# Main_Board.net
KiCad netlist of a schematic drawn in EAGLE
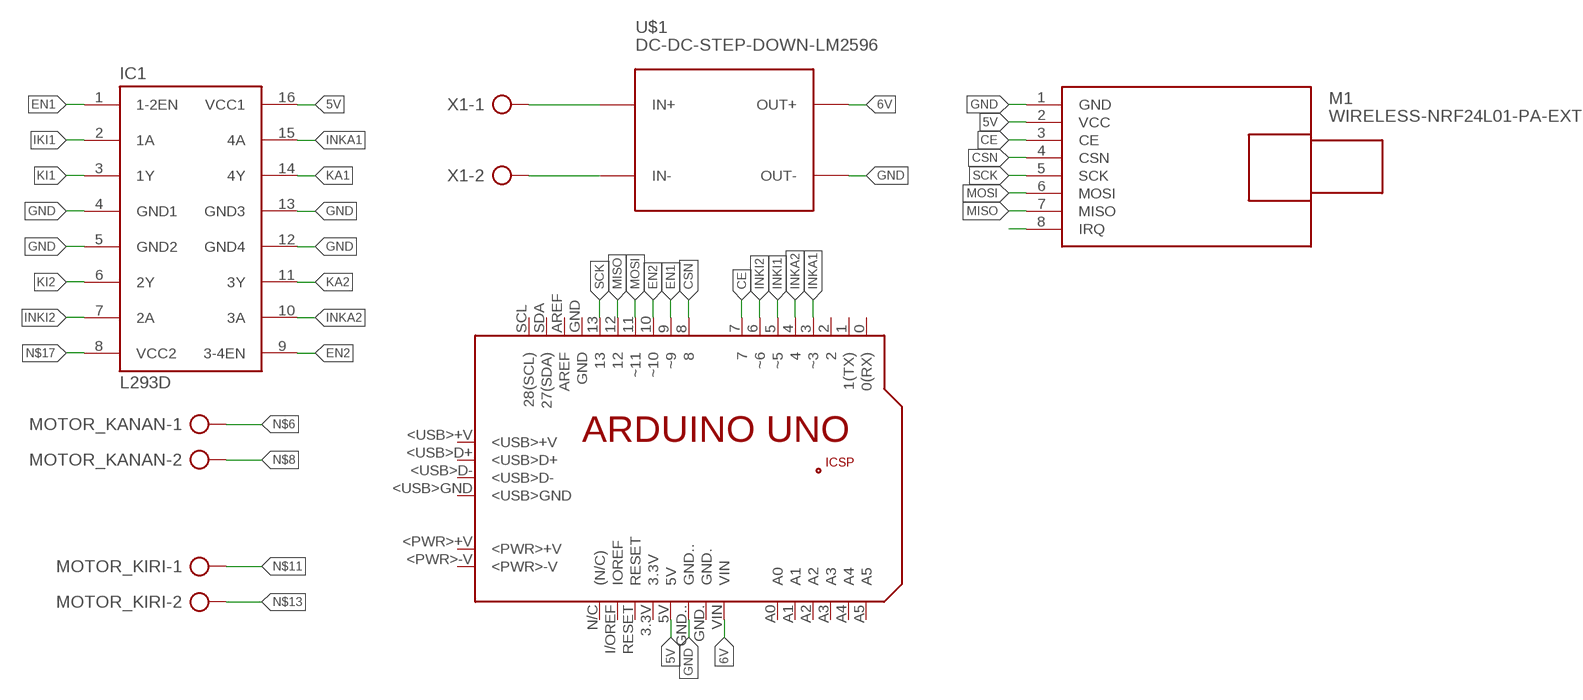
[diagram p0: schematic, sheet 1]

(export (version "E")
  (design (tool "Eeschema 10.0.6"))
  (components
    (comp (ref "IC1")
      (value "L293D")
      (footprint "eagle-import:DIL16")
      (libsource (lib "eagle-import") (part "L293D"))
    )
    (comp (ref "M1")
      (value "WIRELESS-NRF24L01-PA-EXT")
      (footprint "eagle-import:WIRELESS-NRF24L01-PA-EXT")
      (libsource (lib "eagle-import") (part "WIRELESS-NRF24L01-PA-EXT"))
    )
    (comp (ref "MOTOR_KANAN")
      (value "AK500/2-H")
      (footprint "eagle-import:AK500_2-H")
      (libsource (lib "eagle-import") (part "AK500/2-H"))
    )
    (comp (ref "MOTOR_KIRI")
      (value "AK500/2-H")
      (footprint "eagle-import:AK500_2-H")
      (libsource (lib "eagle-import") (part "AK500/2-H"))
    )
    (comp (ref "PCB1")
      (value "ARDUINO_UNO")
      (footprint "eagle-import:ARDUINO_UNO")
      (libsource (lib "eagle-import") (part "ARDUINO_UNO"))
    )
    (comp (ref "U$1")
      (value "DC-DC-STEP-DOWN-LM2596")
      (footprint "eagle-import:DC-DC-STEP-DOWN-LM2596")
      (libsource (lib "eagle-import") (part "DC-DC-STEP-DOWN-LM2596"))
    )
    (comp (ref "X1")
      (value "AK300/2")
      (footprint "eagle-import:AK300_2")
      (libsource (lib "eagle-import") (part "AK300/2"))
    )
  )
  (nets
    (net (code "1") (name "5V") (class "Default")
      (node (ref "IC1") (pin "16") (pinfunction "VCC1_16") (pintype "power_in"))
      (node (ref "M1") (pin "2") (pinfunction "VCC_2") (pintype "power_in"))
      (node (ref "PCB1") (pin "5V") (pinfunction "5V_5V") (pintype "bidirectional"))
    )
    (net (code "2") (name "6V") (class "Default")
      (node (ref "PCB1") (pin "VIN") (pinfunction "VIN_VIN") (pintype "bidirectional"))
      (node (ref "U$1") (pin "OUT+") (pinfunction "OUT+_OUT+") (pintype "bidirectional"))
    )
    (net (code "3") (name "CE") (class "Default")
      (node (ref "M1") (pin "3") (pinfunction "CE_3") (pintype "bidirectional"))
      (node (ref "PCB1") (pin "7") (pinfunction "7_7") (pintype "bidirectional"))
    )
    (net (code "4") (name "CSN") (class "Default")
      (node (ref "M1") (pin "4") (pinfunction "CSN_4") (pintype "bidirectional"))
      (node (ref "PCB1") (pin "8") (pinfunction "8_8") (pintype "bidirectional"))
    )
    (net (code "5") (name "EN1") (class "Default")
      (node (ref "IC1") (pin "1") (pinfunction "1-2EN_1") (pintype "input"))
      (node (ref "PCB1") (pin "9") (pinfunction "~{9}_9") (pintype "bidirectional"))
    )
    (net (code "6") (name "EN2") (class "Default")
      (node (ref "IC1") (pin "9") (pinfunction "3-4EN_9") (pintype "input"))
      (node (ref "PCB1") (pin "10") (pinfunction "~{10}_10") (pintype "bidirectional"))
    )
    (net (code "7") (name "GND") (class "Default")
      (node (ref "IC1") (pin "12") (pinfunction "GND4_12") (pintype "power_in"))
      (node (ref "IC1") (pin "13") (pinfunction "GND3_13") (pintype "power_in"))
      (node (ref "IC1") (pin "4") (pinfunction "GND1_4") (pintype "power_in"))
      (node (ref "IC1") (pin "5") (pinfunction "GND2_5") (pintype "power_in"))
      (node (ref "M1") (pin "1") (pinfunction "GND_1") (pintype "power_in"))
      (node (ref "PCB1") (pin "GND..") (pinfunction "GND.._GND..") (pintype "bidirectional"))
      (node (ref "U$1") (pin "OUT-") (pinfunction "OUT-_OUT-") (pintype "bidirectional"))
    )
    (net (code "8") (name "IKI1") (class "Default")
      (node (ref "IC1") (pin "2") (pinfunction "1A_2") (pintype "input"))
    )
    (net (code "9") (name "INKA1") (class "Default")
      (node (ref "IC1") (pin "15") (pinfunction "4A_15") (pintype "input"))
      (node (ref "PCB1") (pin "3") (pinfunction "~{3}_3") (pintype "bidirectional"))
    )
    (net (code "10") (name "INKA2") (class "Default")
      (node (ref "IC1") (pin "10") (pinfunction "3A_10") (pintype "input"))
      (node (ref "PCB1") (pin "4") (pinfunction "4_4") (pintype "bidirectional"))
    )
    (net (code "11") (name "INKI1") (class "Default")
      (node (ref "PCB1") (pin "5") (pinfunction "~{5}_5") (pintype "bidirectional"))
    )
    (net (code "12") (name "INKI2") (class "Default")
      (node (ref "IC1") (pin "7") (pinfunction "2A_7") (pintype "input"))
      (node (ref "PCB1") (pin "6") (pinfunction "~{6}_6") (pintype "bidirectional"))
    )
    (net (code "13") (name "KA1") (class "Default")
      (node (ref "IC1") (pin "14") (pinfunction "4Y_14") (pintype "output"))
    )
    (net (code "14") (name "KA2") (class "Default")
      (node (ref "IC1") (pin "11") (pinfunction "3Y_11") (pintype "output"))
    )
    (net (code "15") (name "KI1") (class "Default")
      (node (ref "IC1") (pin "3") (pinfunction "1Y_3") (pintype "output"))
    )
    (net (code "16") (name "KI2") (class "Default")
      (node (ref "IC1") (pin "6") (pinfunction "2Y_6") (pintype "output"))
    )
    (net (code "17") (name "MISO") (class "Default")
      (node (ref "M1") (pin "7") (pinfunction "MISO_7") (pintype "bidirectional"))
      (node (ref "PCB1") (pin "12") (pinfunction "12_12") (pintype "bidirectional"))
    )
    (net (code "18") (name "MOSI") (class "Default")
      (node (ref "M1") (pin "6") (pinfunction "MOSI_6") (pintype "bidirectional"))
      (node (ref "PCB1") (pin "11") (pinfunction "~{11}_11") (pintype "bidirectional"))
    )
    (net (code "19") (name "N$6") (class "Default")
      (node (ref "MOTOR_KANAN") (pin "1") (pinfunction "KL_1") (pintype "passive"))
    )
    (net (code "20") (name "N$8") (class "Default")
      (node (ref "MOTOR_KANAN") (pin "2") (pinfunction "KL_2") (pintype "passive"))
    )
    (net (code "21") (name "N$11") (class "Default")
      (node (ref "MOTOR_KIRI") (pin "1") (pinfunction "KL_1") (pintype "passive"))
    )
    (net (code "22") (name "N$13") (class "Default")
      (node (ref "MOTOR_KIRI") (pin "2") (pinfunction "KL_2") (pintype "passive"))
    )
    (net (code "23") (name "N$17") (class "Default")
      (node (ref "IC1") (pin "8") (pinfunction "VCC2_8") (pintype "power_in"))
    )
    (net (code "24") (name "Net-(X1A-KL)") (class "Default")
      (node (ref "U$1") (pin "IN+") (pinfunction "IN+_IN+") (pintype "bidirectional"))
      (node (ref "X1") (pin "1") (pinfunction "KL_1") (pintype "passive"))
    )
    (net (code "25") (name "Net-(X1B-KL)") (class "Default")
      (node (ref "U$1") (pin "IN-") (pinfunction "IN-_IN-") (pintype "bidirectional"))
      (node (ref "X1") (pin "2") (pinfunction "KL_2") (pintype "passive"))
    )
    (net (code "26") (name "SCK") (class "Default")
      (node (ref "M1") (pin "5") (pinfunction "SCK_5") (pintype "bidirectional"))
      (node (ref "PCB1") (pin "13") (pinfunction "13_13") (pintype "bidirectional"))
    )
    (net (code "27") (name "unconnected-(M1-IRQ-Pad8)") (class "Default")
      (node (ref "M1") (pin "8") (pinfunction "IRQ_8") (pintype "bidirectional"))
    )
    (net (code "28") (name "unconnected-(PCB1-(N{slash}C)-PadN{slash}C)") (class "Default")
      (node (ref "PCB1") (pin "N/C") (pinfunction "(N/C)_N/C") (pintype "bidirectional"))
    )
    (net (code "29") (name "unconnected-(PCB1-0(RX)-Pad0)") (class "Default")
      (node (ref "PCB1") (pin "0") (pinfunction "0(RX)_0") (pintype "bidirectional"))
    )
    (net (code "30") (name "unconnected-(PCB1-1(TX)-Pad1)") (class "Default")
      (node (ref "PCB1") (pin "1") (pinfunction "1(TX)_1") (pintype "bidirectional"))
    )
    (net (code "31") (name "unconnected-(PCB1-27(SDA)-PadSDA)") (class "Default")
      (node (ref "PCB1") (pin "SDA") (pinfunction "27(SDA)_SDA") (pintype "bidirectional"))
    )
    (net (code "32") (name "unconnected-(PCB1-28(SCL)-PadSCL)") (class "Default")
      (node (ref "PCB1") (pin "SCL") (pinfunction "28(SCL)_SCL") (pintype "bidirectional"))
    )
    (net (code "33") (name "unconnected-(PCB1-IOREF-PadI{slash}OREF)") (class "Default")
      (node (ref "PCB1") (pin "I/OREF") (pinfunction "IOREF_I/OREF") (pintype "bidirectional"))
    )
    (net (code "34") (name "unconnected-(PCB1-Pad+5V)") (class "Default")
      (node (ref "PCB1") (pin "+5V") (pinfunction "+5V_+5V") (pintype "bidirectional"))
    )
    (net (code "35") (name "unconnected-(PCB1-Pad2)") (class "Default")
      (node (ref "PCB1") (pin "2") (pinfunction "2_2") (pintype "bidirectional"))
    )
    (net (code "36") (name "unconnected-(PCB1-Pad3.3V)") (class "Default")
      (node (ref "PCB1") (pin "3.3V") (pinfunction "3.3V_3.3V") (pintype "bidirectional"))
    )
    (net (code "37") (name "unconnected-(PCB1-Pad<PWR>+V)") (class "Default")
      (node (ref "PCB1") (pin "<PWR>+V") (pinfunction "<PWR>+V_<PWR>+V") (pintype "bidirectional"))
    )
    (net (code "38") (name "unconnected-(PCB1-Pad<PWR>-V)") (class "Default")
      (node (ref "PCB1") (pin "<PWR>-V") (pinfunction "<PWR>-V_<PWR>-V") (pintype "bidirectional"))
    )
    (net (code "39") (name "unconnected-(PCB1-Pad<USB>+V)") (class "Default")
      (node (ref "PCB1") (pin "<USB>+V") (pinfunction "<USB>+V_<USB>+V") (pintype "bidirectional"))
    )
    (net (code "40") (name "unconnected-(PCB1-Pad<USB>D+)") (class "Default")
      (node (ref "PCB1") (pin "<USB>D+") (pinfunction "<USB>D+_<USB>D+") (pintype "bidirectional"))
    )
    (net (code "41") (name "unconnected-(PCB1-Pad<USB>D-)") (class "Default")
      (node (ref "PCB1") (pin "<USB>D-") (pinfunction "<USB>D-_<USB>D-") (pintype "bidirectional"))
    )
    (net (code "42") (name "unconnected-(PCB1-Pad<USB>GND)") (class "Default")
      (node (ref "PCB1") (pin "<USB>GND") (pinfunction "<USB>GND_<USB>GND") (pintype "bidirectional"))
    )
    (net (code "43") (name "unconnected-(PCB1-PadA0)") (class "Default")
      (node (ref "PCB1") (pin "A0") (pinfunction "A0_A0") (pintype "bidirectional"))
    )
    (net (code "44") (name "unconnected-(PCB1-PadA1)") (class "Default")
      (node (ref "PCB1") (pin "A1") (pinfunction "A1_A1") (pintype "bidirectional"))
    )
    (net (code "45") (name "unconnected-(PCB1-PadA2)") (class "Default")
      (node (ref "PCB1") (pin "A2") (pinfunction "A2_A2") (pintype "bidirectional"))
    )
    (net (code "46") (name "unconnected-(PCB1-PadA3)") (class "Default")
      (node (ref "PCB1") (pin "A3") (pinfunction "A3_A3") (pintype "bidirectional"))
    )
    (net (code "47") (name "unconnected-(PCB1-PadA4)") (class "Default")
      (node (ref "PCB1") (pin "A4") (pinfunction "A4_A4") (pintype "bidirectional"))
    )
    (net (code "48") (name "unconnected-(PCB1-PadA5)") (class "Default")
      (node (ref "PCB1") (pin "A5") (pinfunction "A5_A5") (pintype "bidirectional"))
    )
    (net (code "49") (name "unconnected-(PCB1-PadAREF)") (class "Default")
      (node (ref "PCB1") (pin "AREF") (pinfunction "AREF_AREF") (pintype "bidirectional"))
    )
    (net (code "50") (name "unconnected-(PCB1-PadGND)") (class "Default")
      (node (ref "PCB1") (pin "GND") (pinfunction "GND_GND") (pintype "bidirectional"))
    )
    (net (code "51") (name "unconnected-(PCB1-PadGND.)") (class "Default")
      (node (ref "PCB1") (pin "GND.") (pinfunction "GND._GND.") (pintype "bidirectional"))
    )
    (net (code "52") (name "unconnected-(PCB1-PadGND_)") (class "Default")
      (node (ref "PCB1") (pin "GND_") (pinfunction "GND__GND_") (pintype "bidirectional"))
    )
    (net (code "53") (name "unconnected-(PCB1-PadMISO)") (class "Default")
      (node (ref "PCB1") (pin "MISO") (pinfunction "MISO_MISO") (pintype "bidirectional"))
    )
    (net (code "54") (name "unconnected-(PCB1-PadMOSI)") (class "Default")
      (node (ref "PCB1") (pin "MOSI") (pinfunction "MOSI_MOSI") (pintype "bidirectional"))
    )
    (net (code "55") (name "unconnected-(PCB1-PadRESET)") (class "Default")
      (node (ref "PCB1") (pin "RESET") (pinfunction "RESET_RESET") (pintype "bidirectional"))
    )
    (net (code "56") (name "unconnected-(PCB1-PadRESET.)") (class "Default")
      (node (ref "PCB1") (pin "RESET.") (pinfunction "RESET._RESET.") (pintype "bidirectional"))
    )
    (net (code "57") (name "unconnected-(PCB1-PadSCK)") (class "Default")
      (node (ref "PCB1") (pin "SCK") (pinfunction "SCK_SCK") (pintype "bidirectional"))
    )
  )
)
